# Engine_Room_Power_Half.net
KiCad netlist of a schematic drawn in EAGLE
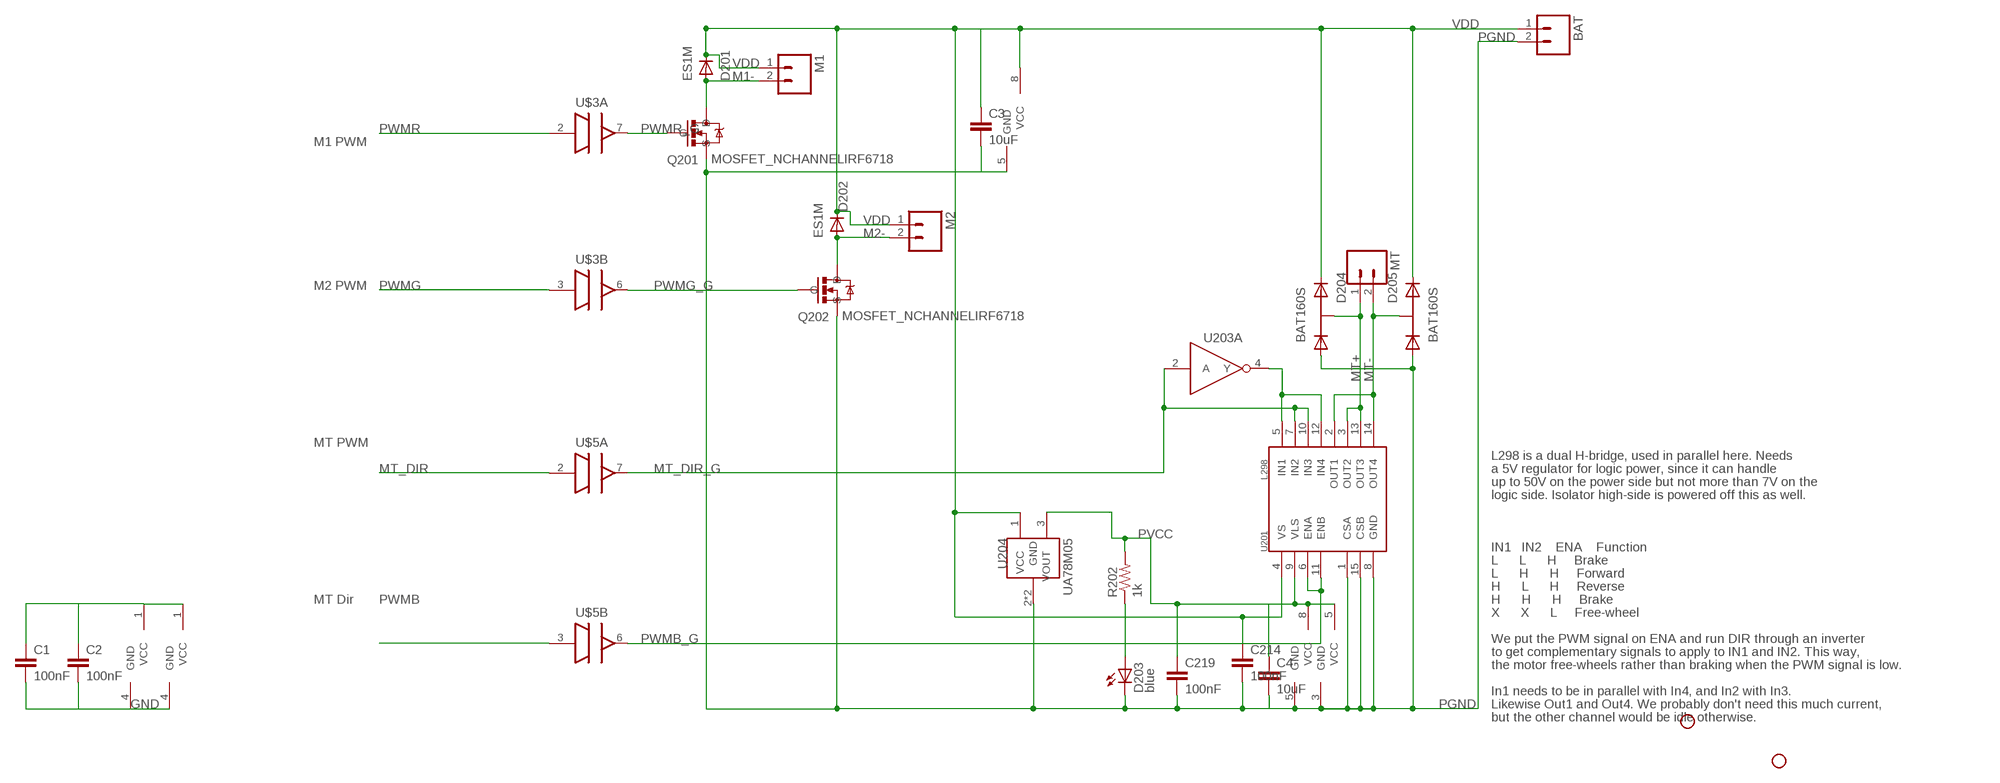
[diagram p0: schematic, sheet 1]

(export (version "E")
  (design (tool "Eeschema 10.0.6"))
  (components
    (comp (ref "BAT")
      (value "M02PTH4")
      (footprint "eagle-import:1X02_XTRA_BIG")
      (libsource (lib "eagle-import") (part "M02PTH4"))
    )
    (comp (ref "C1")
      (value "100nF")
      (footprint "eagle-import:0402-CAP")
      (libsource (lib "eagle-import") (part "CAP0402-CAP"))
    )
    (comp (ref "C2")
      (value "100nF")
      (footprint "eagle-import:0402-CAP")
      (libsource (lib "eagle-import") (part "CAP0402-CAP"))
    )
    (comp (ref "C3")
      (value "10uF")
      (footprint "eagle-import:1206")
      (libsource (lib "eagle-import") (part "SparkFun-Passives_CAP1206"))
    )
    (comp (ref "C4")
      (value "10uF")
      (footprint "eagle-import:1206")
      (libsource (lib "eagle-import") (part "SparkFun-Passives_CAP1206"))
    )
    (comp (ref "C214")
      (value "100nF")
      (footprint "eagle-import:1206")
      (libsource (lib "eagle-import") (part "SparkFun-Passives_CAP1206"))
    )
    (comp (ref "C219")
      (value "100nF")
      (footprint "eagle-import:0402-CAP")
      (libsource (lib "eagle-import") (part "CAP0402-CAP"))
    )
    (comp (ref "D201")
      (value "ES1M")
      (footprint "eagle-import:DO-214AC")
      (libsource (lib "eagle-import") (part "DIODE-DO-214AC"))
    )
    (comp (ref "D202")
      (value "ES1M")
      (footprint "eagle-import:DO-214AC")
      (libsource (lib "eagle-import") (part "DIODE-DO-214AC"))
    )
    (comp (ref "D203")
      (value "blue")
      (footprint "eagle-import:LED-0603")
      (libsource (lib "eagle-import") (part "LED0603"))
    )
    (comp (ref "D204")
      (value "BAT160S")
      (footprint "eagle-import:SOT-223")
      (libsource (lib "eagle-import") (part "BAT160S"))
    )
    (comp (ref "D205")
      (value "BAT160S")
      (footprint "eagle-import:SOT-223")
      (libsource (lib "eagle-import") (part "BAT160S"))
    )
    (comp (ref "JP1")
      (value "STAND-OFF")
      (footprint "eagle-import:STAND-OFF")
      (libsource (lib "eagle-import") (part "STAND-OFF"))
    )
    (comp (ref "JP2")
      (value "STAND-OFF")
      (footprint "eagle-import:STAND-OFF")
      (libsource (lib "eagle-import") (part "STAND-OFF"))
    )
    (comp (ref "M1")
      (value "M02PTH4")
      (footprint "eagle-import:1X02_XTRA_BIG")
      (libsource (lib "eagle-import") (part "M02PTH4"))
    )
    (comp (ref "M2")
      (value "M02PTH4")
      (footprint "eagle-import:1X02_XTRA_BIG")
      (libsource (lib "eagle-import") (part "M02PTH4"))
    )
    (comp (ref "MT")
      (value "M02PTH")
      (footprint "eagle-import:1X02")
      (libsource (lib "eagle-import") (part "M02PTH"))
    )
    (comp (ref "Q201")
      (value "MOSFET_NCHANNELIRF6718")
      (footprint "eagle-import:DIRECTFET_L6")
      (libsource (lib "eagle-import") (part "MOSFET_NCHANNELIRF6718"))
    )
    (comp (ref "Q202")
      (value "MOSFET_NCHANNELIRF6718")
      (footprint "eagle-import:DIRECTFET_L6")
      (libsource (lib "eagle-import") (part "MOSFET_NCHANNELIRF6718"))
    )
    (comp (ref "R202")
      (value "1k")
      (footprint "eagle-import:0402-RES")
      (libsource (lib "eagle-import") (part "RESISTOR0402-RES"))
    )
    (comp (ref "U$3")
      (value "ADUM3221")
      (footprint "eagle-import:SO8N")
      (libsource (lib "eagle-import") (part "ADUM3221"))
    )
    (comp (ref "U$5")
      (value "ADUM3221")
      (footprint "eagle-import:SO8N")
      (libsource (lib "eagle-import") (part "ADUM3221"))
    )
    (comp (ref "U201")
      (value "L298")
      (footprint "eagle-import:MULTIWATT15")
      (libsource (lib "eagle-import") (part "L298"))
    )
    (comp (ref "U203")
      (value "MC74VHC1G04")
      (footprint "eagle-import:SOT-23-5")
      (libsource (lib "eagle-import") (part "MC74VHC1G04"))
    )
    (comp (ref "U204")
      (value "UA78M05")
      (footprint "eagle-import:SOT-223")
      (libsource (lib "eagle-import") (part "UA78M05"))
    )
  )
  (nets
    (net (code "1") (name "/GND") (class "Default")
      (node (ref "C1") (pin "2") (pinfunction "2_2") (pintype "passive"))
      (node (ref "C2") (pin "2") (pinfunction "2_2") (pintype "passive"))
      (node (ref "U$3") (pin "4") (pinfunction "GND_4") (pintype "bidirectional"))
      (node (ref "U$5") (pin "4") (pinfunction "GND_4") (pintype "bidirectional"))
    )
    (net (code "2") (name "/M1-") (class "Default")
      (node (ref "D201") (pin "A") (pinfunction "A_A") (pintype "passive"))
      (node (ref "M1") (pin "2") (pinfunction "2_2") (pintype "passive"))
      (node (ref "Q201") (pin "D1") (pinfunction "D_D1") (pintype "passive"))
      (node (ref "Q201") (pin "D2") (pinfunction "D_D2") (pintype "passive"))
    )
    (net (code "3") (name "/M2-") (class "Default")
      (node (ref "D202") (pin "A") (pinfunction "A_A") (pintype "passive"))
      (node (ref "M2") (pin "2") (pinfunction "2_2") (pintype "passive"))
      (node (ref "Q202") (pin "D1") (pinfunction "D_D1") (pintype "passive"))
      (node (ref "Q202") (pin "D2") (pinfunction "D_D2") (pintype "passive"))
    )
    (net (code "4") (name "/MT+") (class "Default")
      (node (ref "D204") (pin "4") (pinfunction "K1A2_4") (pintype "passive"))
      (node (ref "MT") (pin "1") (pinfunction "1_1") (pintype "passive"))
      (node (ref "U201") (pin "13") (pinfunction "OUT3_13") (pintype "bidirectional"))
      (node (ref "U201") (pin "3") (pinfunction "OUT2_3") (pintype "bidirectional"))
    )
    (net (code "5") (name "/MT-") (class "Default")
      (node (ref "D205") (pin "4") (pinfunction "K1A2_4") (pintype "passive"))
      (node (ref "MT") (pin "2") (pinfunction "2_2") (pintype "passive"))
      (node (ref "U201") (pin "14") (pinfunction "OUT4_14") (pintype "bidirectional"))
      (node (ref "U201") (pin "2") (pinfunction "OUT1_2") (pintype "bidirectional"))
    )
    (net (code "6") (name "/MT_DIR") (class "Default")
      (node (ref "U$5") (pin "2") (pinfunction "IN_2") (pintype "input"))
    )
    (net (code "7") (name "/MT_DIR_G") (class "Default")
      (node (ref "U$5") (pin "7") (pinfunction "OUT_7") (pintype "bidirectional"))
      (node (ref "U201") (pin "10") (pinfunction "IN3_10") (pintype "bidirectional"))
      (node (ref "U201") (pin "7") (pinfunction "IN2_7") (pintype "bidirectional"))
      (node (ref "U203") (pin "2") (pinfunction "A_2") (pintype "input"))
    )
    (net (code "8") (name "/PGND") (class "Default")
      (node (ref "BAT") (pin "2") (pinfunction "2_2") (pintype "passive"))
      (node (ref "C214") (pin "2") (pinfunction "2_2") (pintype "passive"))
      (node (ref "C219") (pin "2") (pinfunction "2_2") (pintype "passive"))
      (node (ref "C3") (pin "2") (pinfunction "2_2") (pintype "passive"))
      (node (ref "C4") (pin "2") (pinfunction "2_2") (pintype "passive"))
      (node (ref "D203") (pin "C") (pinfunction "C_C") (pintype "passive"))
      (node (ref "D204") (pin "1") (pinfunction "A1_1") (pintype "passive"))
      (node (ref "D205") (pin "1") (pinfunction "A1_1") (pintype "passive"))
      (node (ref "Q201") (pin "S") (pinfunction "S_S") (pintype "passive"))
      (node (ref "Q202") (pin "S") (pinfunction "S_S") (pintype "passive"))
      (node (ref "U$3") (pin "5") (pinfunction "GND_5") (pintype "bidirectional"))
      (node (ref "U$5") (pin "5") (pinfunction "GND_5") (pintype "bidirectional"))
      (node (ref "U201") (pin "1") (pinfunction "CSA_1") (pintype "bidirectional"))
      (node (ref "U201") (pin "15") (pinfunction "CSB_15") (pintype "bidirectional"))
      (node (ref "U201") (pin "8") (pinfunction "GND_8") (pintype "bidirectional"))
      (node (ref "U203") (pin "3") (pinfunction "GND_3") (pintype "bidirectional"))
      (node (ref "U204") (pin "2") (pinfunction "GND_2") (pintype "bidirectional"))
      (node (ref "U204") (pin "4") (pinfunction "GND_4") (pintype "bidirectional"))
    )
    (net (code "9") (name "/PVCC") (class "Default")
      (node (ref "C219") (pin "1") (pinfunction "1_1") (pintype "passive"))
      (node (ref "C4") (pin "1") (pinfunction "1_1") (pintype "passive"))
      (node (ref "R202") (pin "2") (pinfunction "2_2") (pintype "passive"))
      (node (ref "U$5") (pin "8") (pinfunction "VCC_8") (pintype "bidirectional"))
      (node (ref "U201") (pin "9") (pinfunction "VLS_9") (pintype "bidirectional"))
      (node (ref "U203") (pin "5") (pinfunction "VCC_5") (pintype "bidirectional"))
      (node (ref "U204") (pin "3") (pinfunction "VOUT_3") (pintype "bidirectional"))
    )
    (net (code "10") (name "/PWMB") (class "Default")
      (node (ref "U$5") (pin "3") (pinfunction "IN_3") (pintype "input"))
    )
    (net (code "11") (name "/PWMB_G") (class "Default")
      (node (ref "U$5") (pin "6") (pinfunction "OUT_6") (pintype "bidirectional"))
      (node (ref "U201") (pin "11") (pinfunction "ENB_11") (pintype "bidirectional"))
      (node (ref "U201") (pin "6") (pinfunction "ENA_6") (pintype "bidirectional"))
    )
    (net (code "12") (name "/PWMG") (class "Default")
      (node (ref "U$3") (pin "3") (pinfunction "IN_3") (pintype "input"))
    )
    (net (code "13") (name "/PWMG_G") (class "Default")
      (node (ref "Q202") (pin "G") (pinfunction "G_G") (pintype "passive"))
      (node (ref "U$3") (pin "6") (pinfunction "OUT_6") (pintype "bidirectional"))
    )
    (net (code "14") (name "/PWMR") (class "Default")
      (node (ref "U$3") (pin "2") (pinfunction "IN_2") (pintype "input"))
    )
    (net (code "15") (name "/PWMR_G") (class "Default")
      (node (ref "Q201") (pin "G") (pinfunction "G_G") (pintype "passive"))
      (node (ref "U$3") (pin "7") (pinfunction "OUT_7") (pintype "bidirectional"))
    )
    (net (code "16") (name "/VDD") (class "Default")
      (node (ref "BAT") (pin "1") (pinfunction "1_1") (pintype "passive"))
      (node (ref "C214") (pin "1") (pinfunction "1_1") (pintype "passive"))
      (node (ref "C3") (pin "1") (pinfunction "1_1") (pintype "passive"))
      (node (ref "D201") (pin "C") (pinfunction "C_C") (pintype "passive"))
      (node (ref "D202") (pin "C") (pinfunction "C_C") (pintype "passive"))
      (node (ref "D204") (pin "3") (pinfunction "K2_3") (pintype "passive"))
      (node (ref "D205") (pin "3") (pinfunction "K2_3") (pintype "passive"))
      (node (ref "M1") (pin "1") (pinfunction "1_1") (pintype "passive"))
      (node (ref "M2") (pin "1") (pinfunction "1_1") (pintype "passive"))
      (node (ref "U$3") (pin "8") (pinfunction "VCC_8") (pintype "bidirectional"))
      (node (ref "U201") (pin "4") (pinfunction "VS_4") (pintype "bidirectional"))
      (node (ref "U204") (pin "1") (pinfunction "VCC_1") (pintype "bidirectional"))
    )
    (net (code "17") (name "Net-(D203-PadA)") (class "Default")
      (node (ref "D203") (pin "A") (pinfunction "A_A") (pintype "passive"))
      (node (ref "R202") (pin "1") (pinfunction "1_1") (pintype "passive"))
    )
    (net (code "18") (name "Net-(U$3C-VCC)") (class "Default")
      (node (ref "C1") (pin "1") (pinfunction "1_1") (pintype "passive"))
      (node (ref "C2") (pin "1") (pinfunction "1_1") (pintype "passive"))
      (node (ref "U$3") (pin "1") (pinfunction "VCC_1") (pintype "bidirectional"))
      (node (ref "U$5") (pin "1") (pinfunction "VCC_1") (pintype "bidirectional"))
    )
    (net (code "19") (name "Net-(U201-IN1)") (class "Default")
      (node (ref "U201") (pin "12") (pinfunction "IN4_12") (pintype "bidirectional"))
      (node (ref "U201") (pin "5") (pinfunction "IN1_5") (pintype "bidirectional"))
      (node (ref "U203") (pin "4") (pinfunction "Y_4") (pintype "output"))
    )
  )
)
